# HV.net
KiCad netlist of a schematic drawn in Altium Designer
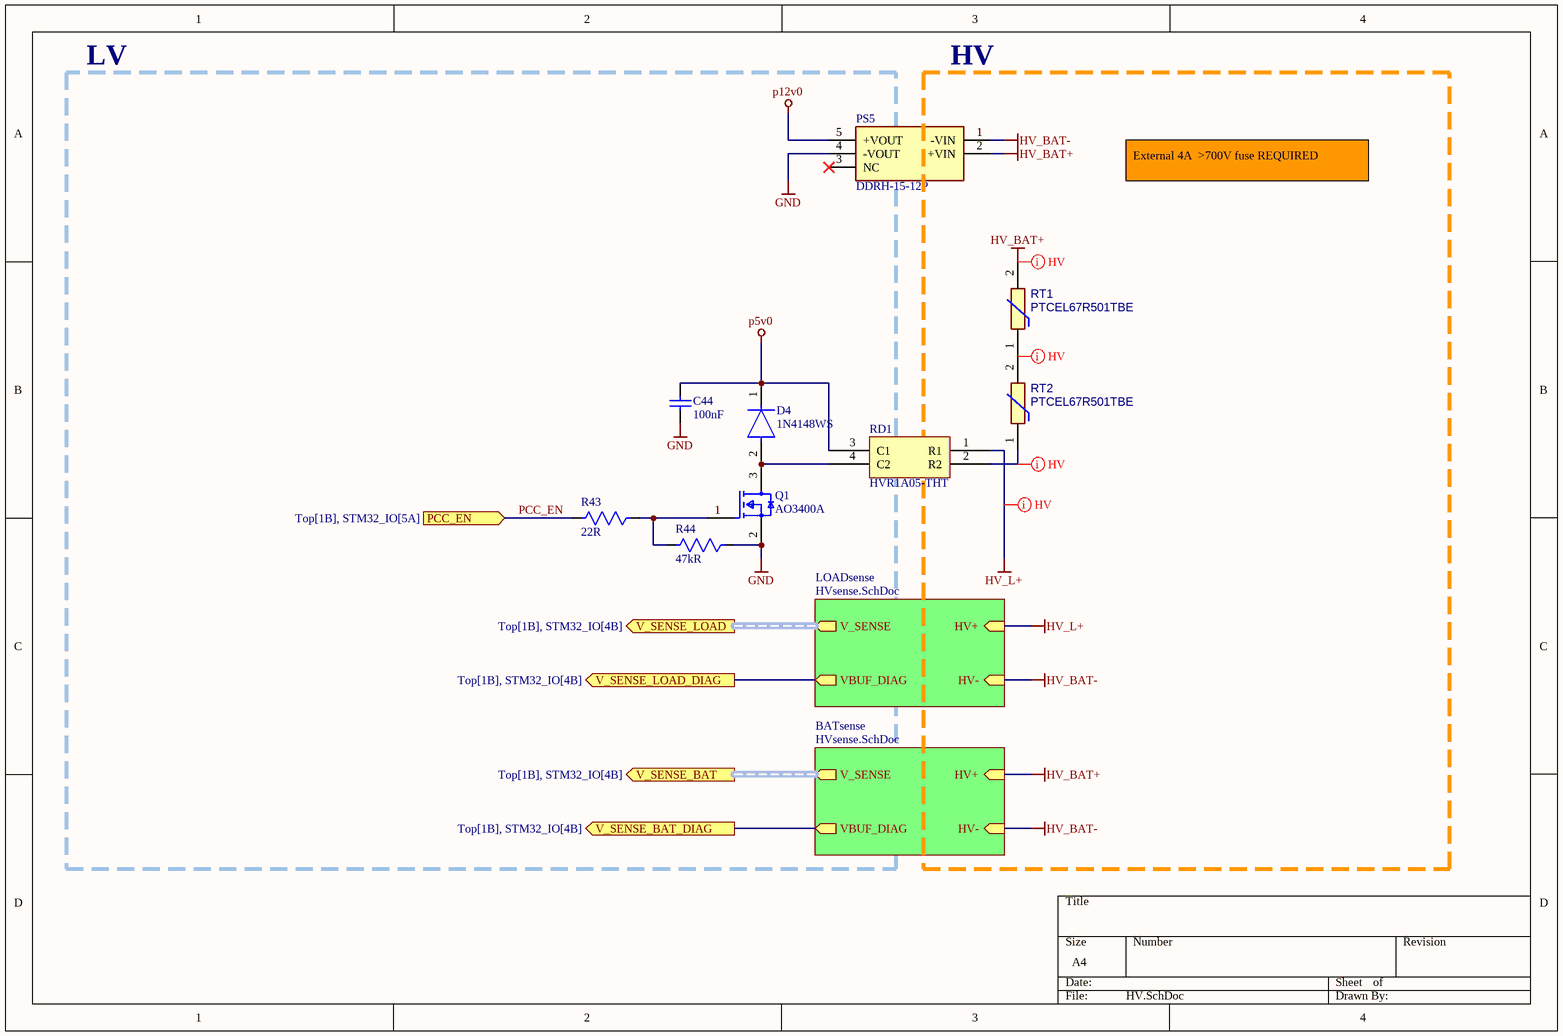
[diagram p0: HV.SchDoc]

(export (version "E")
  (design (tool "Eeschema 10.0.6"))
  (components
    (comp (ref "C44")
      (value "100nF")
      (footprint "WCAP-CSGP_0603_L1.6W0.8H0.8_Reflow")
      (description "GTT Standard 0603 non-polarized capacitor")
      (fields (field (name "JLCPCB PART #") "C14663") (field (name "Comment") "CAP 0603 100nF X7R"))
      (libsource (lib "Green Team Twente") (part "CAP_NONPOL_GENERIC"))
    )
    (comp (ref "D4")
      (value "1N4148WS")
      (footprint "FP-477AB-IPC_C")
      (description "DIODE GEN PURP 75V 150MA SOD323F")
      (libsource (lib "Altium Content Vault") (part "d7152d700b627762746794eb795d46e"))
    )
    (comp (ref "PS5")
      (value "DDRH-15-12P")
      (footprint "DDRH1512P")
      (description "Power Supply")
      (libsource (lib "FlexBMS_lib") (part "DDRH-15-12P"))
    )
    (comp (ref "Q1")
      (value "AO3400A")
      (footprint "FP-SOT23-MFG")
      (description "MOSFET N-CH 30V 5.7A SOT23")
      (libsource (lib "Altium Content Vault") (part "0a9ea7c96deaaede766a5b531c28de0"))
    )
    (comp (ref "R43")
      (value "22R")
      (footprint "RES_SM0603_YAGEORC_N")
      (description "GTT Standard 0603 Resistor")
      (fields (field (name "POWER") "62.5mW") (field (name "TOLERANCE") "1%"))
      (libsource (lib "Green Team Twente") (part "RES_GENERIC"))
    )
    (comp (ref "R44")
      (value "47kR")
      (footprint "RES_SM0603_YAGEORC_N")
      (description "GTT Standard 0603 Resistor")
      (fields (field (name "POWER") "62.5mW") (field (name "TOLERANCE") "1%"))
      (libsource (lib "Green Team Twente") (part "RES_GENERIC"))
    )
    (comp (ref "RD1")
      (value "HVR1A05-THT")
      (footprint "HVR1A05-THT")
      (libsource (lib "FlexBMS_lib") (part "HVR1A05-THT"))
    )
    (comp (ref "RT1")
      (value "PTCEL67R501TBE")
      (footprint "PTCEL67R501TBE-Footprint-1")
      (description "VISHAY - PTCEL67R501TBE - PTC THERMISTOR")
      (fields (field (name "JLCPCB PART #") "C23949633"))
      (libsource (lib "Green Team Twente") (part "PTCEL67R501TBE"))
    )
    (comp (ref "RT2")
      (value "PTCEL67R501TBE")
      (footprint "PTCEL67R501TBE-Footprint-1")
      (description "VISHAY - PTCEL67R501TBE - PTC THERMISTOR")
      (fields (field (name "JLCPCB PART #") "C23949633"))
      (libsource (lib "Green Team Twente") (part "PTCEL67R501TBE"))
    )
  )
  (nets
    (net (code "1") (name "/PCC_EN") (class "Default")
      (node (ref "R43") (pin "2") (pinfunction "2_2") (pintype "passive"))
    )
    (net (code "6") (name "GND") (class "Default")
      (node (ref "C44") (pin "2") (pinfunction "2_2") (pintype "passive"))
      (node (ref "PS5") (pin "4") (pinfunction "-VOUT_4") (pintype "passive"))
      (node (ref "Q1") (pin "2") (pinfunction "S_2") (pintype "passive"))
      (node (ref "R44") (pin "1") (pinfunction "1_1") (pintype "passive"))
    )
    (net (code "7") (name "HV_BAT+") (class "Default")
      (node (ref "PS5") (pin "2") (pinfunction "+VIN_2") (pintype "passive"))
      (node (ref "RT1") (pin "2") (pinfunction "2_2") (pintype "passive"))
    )
    (net (code "8") (name "HV_BAT-") (class "Default")
      (node (ref "PS5") (pin "1") (pinfunction "-VIN_1") (pintype "passive"))
    )
    (net (code "9") (name "HV_L+") (class "Default")
      (node (ref "RD1") (pin "1") (pinfunction "R1_1") (pintype "passive"))
    )
    (net (code "10") (name "Net-(D4-A)") (class "Default")
      (node (ref "D4") (pin "2") (pinfunction "A_2") (pintype "passive"))
      (node (ref "Q1") (pin "3") (pinfunction "D_3") (pintype "passive"))
      (node (ref "RD1") (pin "4") (pinfunction "C2_4") (pintype "passive"))
    )
    (net (code "11") (name "Net-(Q1-G)") (class "Default")
      (node (ref "Q1") (pin "1") (pinfunction "G_1") (pintype "passive"))
      (node (ref "R43") (pin "1") (pinfunction "1_1") (pintype "passive"))
      (node (ref "R44") (pin "2") (pinfunction "2_2") (pintype "passive"))
    )
    (net (code "12") (name "Net-(RD1-R2)") (class "Default")
      (node (ref "RD1") (pin "2") (pinfunction "R2_2") (pintype "passive"))
      (node (ref "RT2") (pin "1") (pinfunction "1_1") (pintype "passive"))
    )
    (net (code "13") (name "Net-(RT1-Pad1)") (class "Default")
      (node (ref "RT1") (pin "1") (pinfunction "1_1") (pintype "passive"))
      (node (ref "RT2") (pin "2") (pinfunction "2_2") (pintype "passive"))
    )
    (net (code "14") (name "p5v0") (class "Default")
      (node (ref "C44") (pin "1") (pinfunction "1_1") (pintype "passive"))
      (node (ref "D4") (pin "1") (pinfunction "C_1") (pintype "passive"))
      (node (ref "RD1") (pin "3") (pinfunction "C1_3") (pintype "passive"))
    )
    (net (code "15") (name "p12v0") (class "Default")
      (node (ref "PS5") (pin "5") (pinfunction "+VOUT_5") (pintype "passive"))
    )
    (net (code "16") (name "unconnected-(PS5-NC-Pad3)") (class "Default")
      (node (ref "PS5") (pin "3") (pinfunction "NC_3") (pintype "passive+no_connect"))
    )
  )
)
